# SCH_RiberyController_2024-03-02.net
KiCad netlist of a schematic drawn in EasyEDA
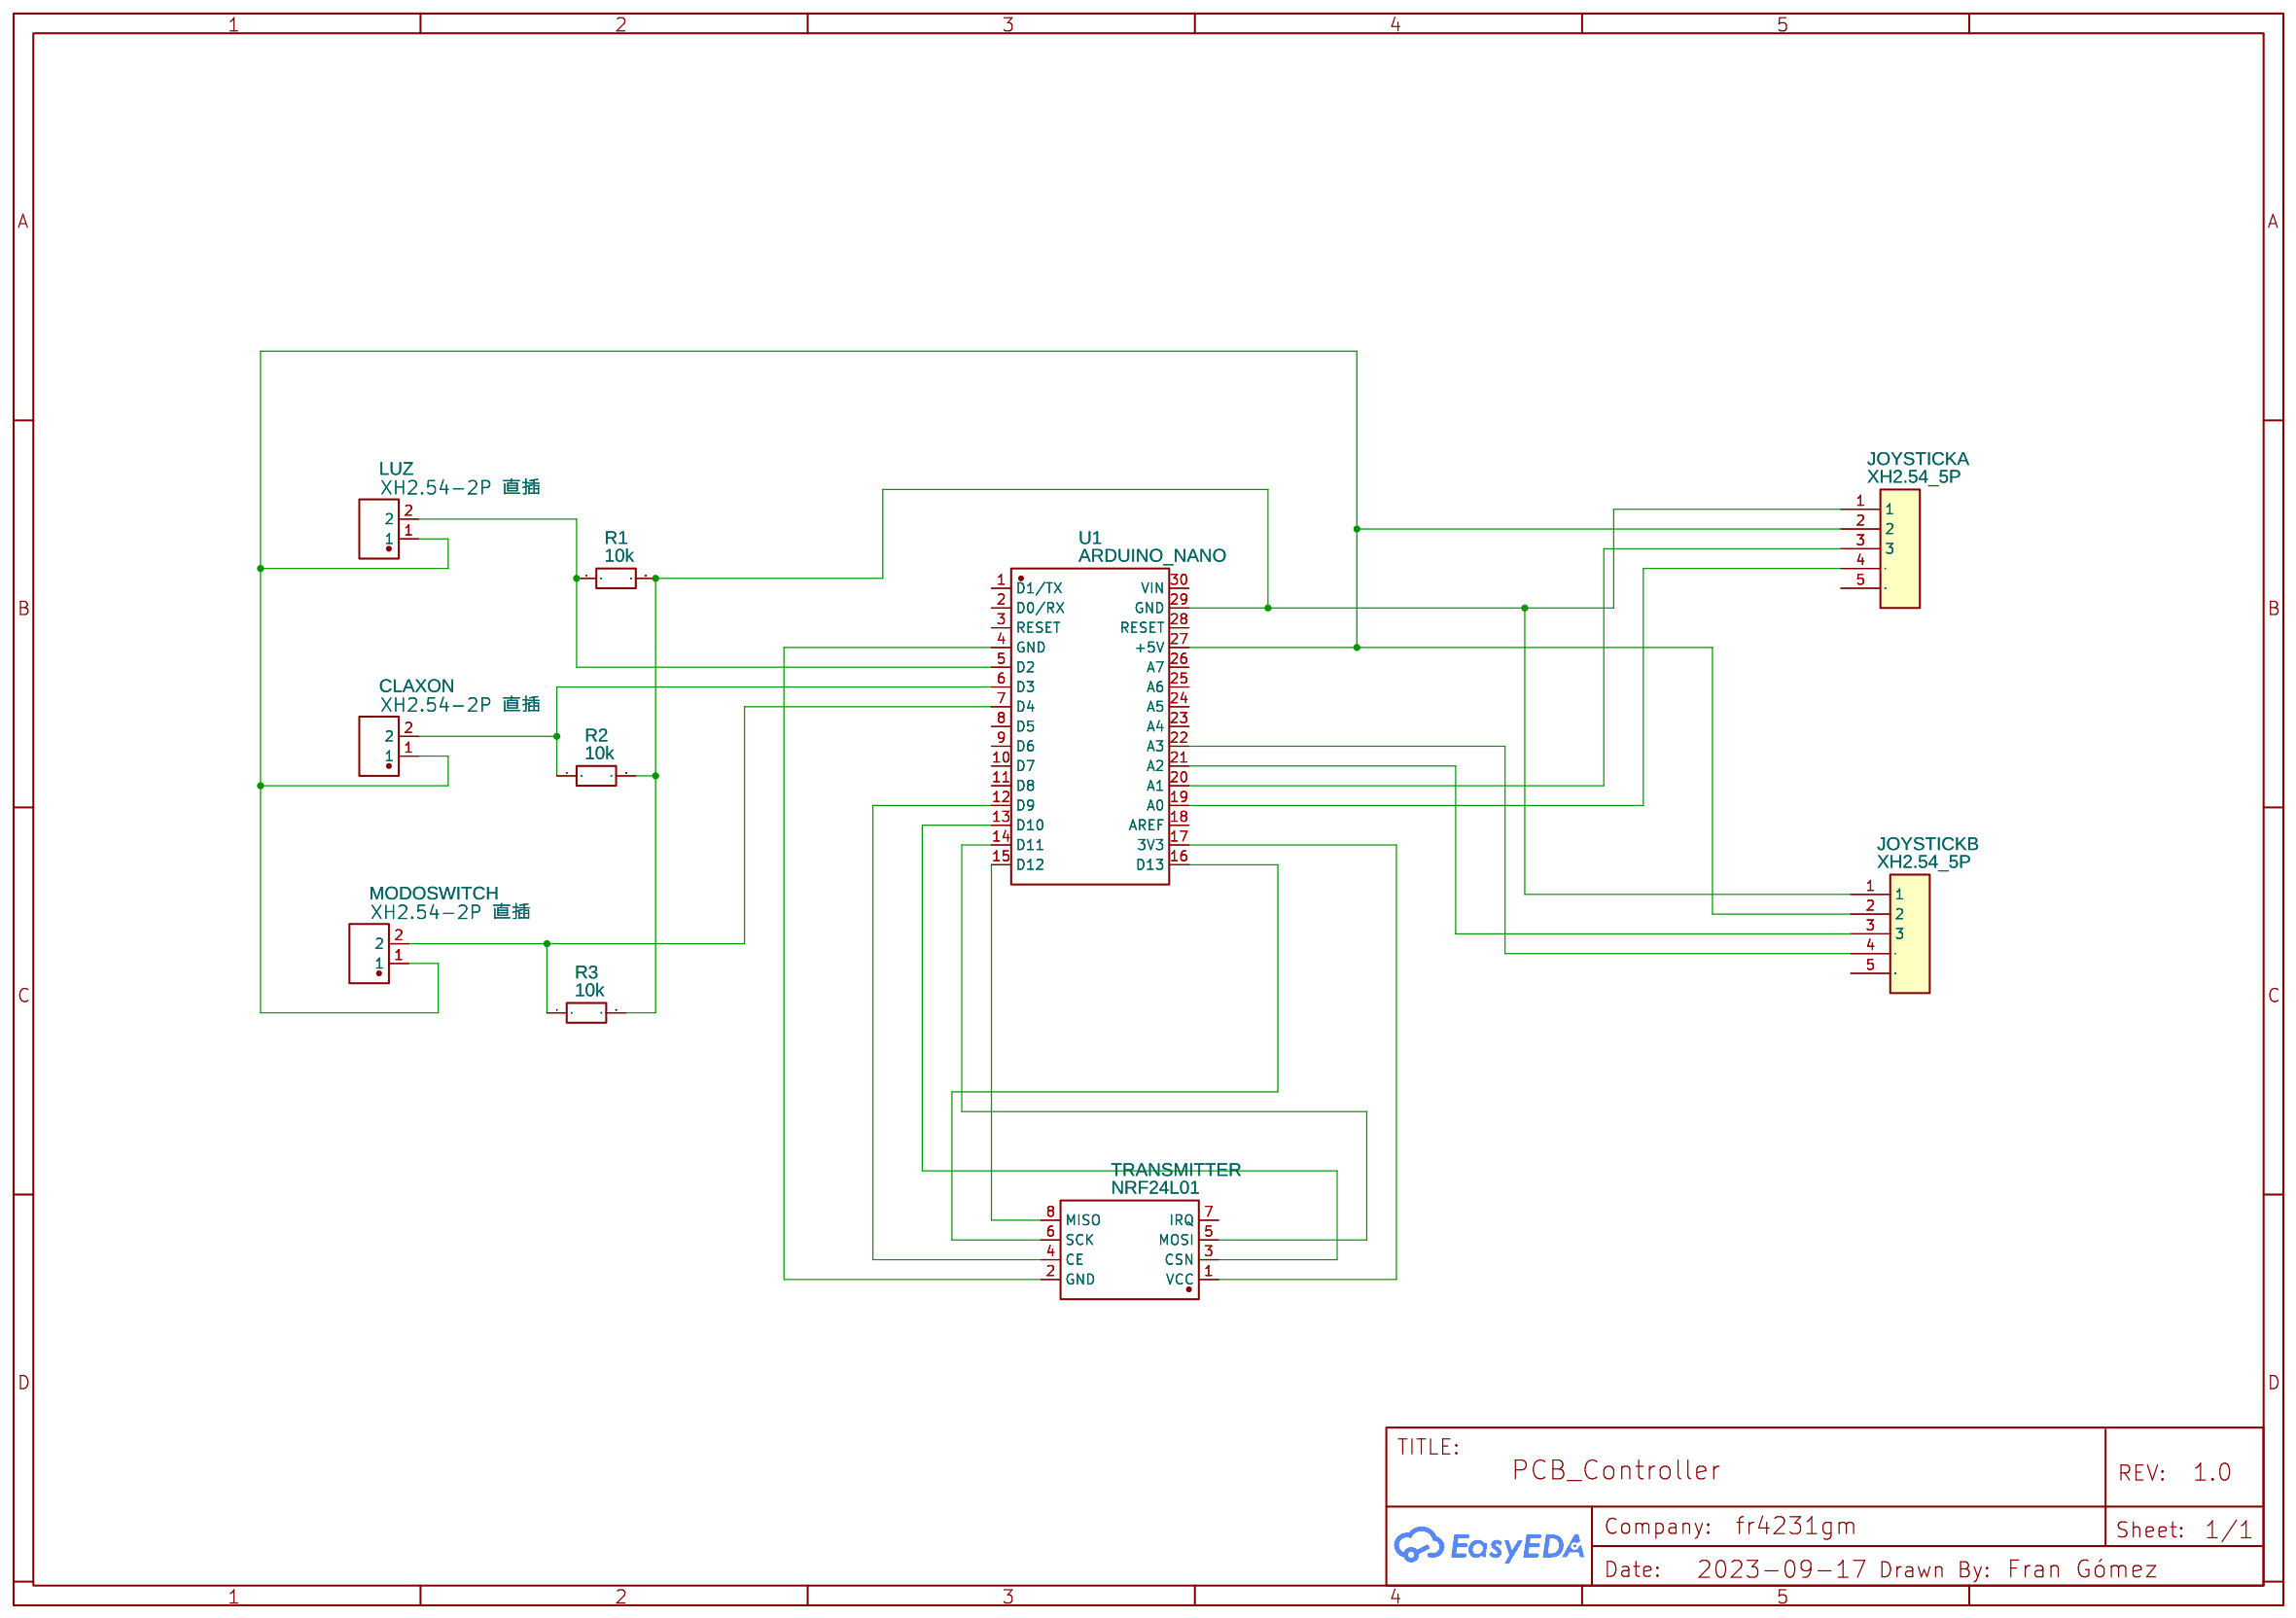
[diagram p0: schematic sheet]

(export (version "E")
  (design (tool "Eeschema 10.0.6"))
  (components
    (comp (ref "CLAXON") (value "XH2.54-2P 直插") (libsource (lib "") (part "XH2.54-2P 直插_2")))
    (comp (ref "JOYSTICKA")
      (value "XH2.54_5P")
      (fields (field (name "Manufacturer Part") "XH2.54_3P"))
      (libsource (lib "") (part "XH2.54_5P_1"))
    )
    (comp (ref "JOYSTICKB")
      (value "XH2.54_5P")
      (fields (field (name "Manufacturer Part") "XH2.54_3P"))
      (libsource (lib "") (part "XH2.54_5P"))
    )
    (comp (ref "LUZ") (value "XH2.54-2P 直插") (libsource (lib "") (part "XH2.54-2P 直插")))
    (comp (ref "MODOSWITCH") (value "XH2.54-2P 直插") (libsource (lib "") (part "XH2.54-2P 直插_1")))
    (comp (ref "R1") (value "10k") (libsource (lib "") (part "R_AXIAL-0.3_EU")))
    (comp (ref "R2") (value "10k") (libsource (lib "") (part "R_AXIAL-0.3_EU")))
    (comp (ref "R3") (value "10k") (libsource (lib "") (part "R_AXIAL-0.3_EU")))
    (comp (ref "TRANSMITTER")
      (value "NRF24L01")
      (fields (field (name "Manufacturer Part") "NF-04") (field (name "Manufacturer") "Ai-Thinker(安信可)"))
      (libsource (lib "") (part "NRF24L01"))
    )
    (comp (ref "U1") (value "ARDUINO_NANO") (libsource (lib "") (part "ARDUINO_NANO")))
  )
  (nets
    (net (code "1") (name "Net-(JOYSTICKA-Pad1)") (class "Default")
      (node (ref "JOYSTICKA") (pin "1") (pinfunction "1_1") (pintype "unspecified"))
      (node (ref "JOYSTICKB") (pin "1") (pinfunction "1_1") (pintype "unspecified"))
      (node (ref "R1") (pin "2") (pinfunction "2_2") (pintype "unspecified"))
      (node (ref "R2") (pin "2") (pinfunction "2_2") (pintype "unspecified"))
      (node (ref "R3") (pin "2") (pinfunction "2_2") (pintype "unspecified"))
      (node (ref "U1") (pin "29") (pinfunction "GND_29") (pintype "unspecified"))
    )
    (net (code "2") (name "Net-(TRANSMITTER-CE)") (class "Default")
      (node (ref "TRANSMITTER") (pin "4") (pinfunction "CE_4") (pintype "unspecified"))
      (node (ref "U1") (pin "12") (pinfunction "D9_12") (pintype "unspecified"))
    )
    (net (code "3") (name "Net-(TRANSMITTER-CSN)") (class "Default")
      (node (ref "TRANSMITTER") (pin "3") (pinfunction "CSN_3") (pintype "unspecified"))
      (node (ref "U1") (pin "13") (pinfunction "D10_13") (pintype "unspecified"))
    )
    (net (code "4") (name "Net-(TRANSMITTER-GND)") (class "Default")
      (node (ref "TRANSMITTER") (pin "2") (pinfunction "GND_2") (pintype "unspecified"))
      (node (ref "U1") (pin "4") (pinfunction "GND_4") (pintype "unspecified"))
    )
    (net (code "5") (name "Net-(TRANSMITTER-MISO)") (class "Default")
      (node (ref "TRANSMITTER") (pin "8") (pinfunction "MISO_8") (pintype "unspecified"))
      (node (ref "U1") (pin "15") (pinfunction "D12_15") (pintype "unspecified"))
    )
    (net (code "6") (name "Net-(TRANSMITTER-MOSI)") (class "Default")
      (node (ref "TRANSMITTER") (pin "5") (pinfunction "MOSI_5") (pintype "unspecified"))
      (node (ref "U1") (pin "14") (pinfunction "D11_14") (pintype "unspecified"))
    )
    (net (code "7") (name "Net-(TRANSMITTER-SCK)") (class "Default")
      (node (ref "TRANSMITTER") (pin "6") (pinfunction "SCK_6") (pintype "unspecified"))
      (node (ref "U1") (pin "16") (pinfunction "D13_16") (pintype "unspecified"))
    )
    (net (code "8") (name "Net-(TRANSMITTER-VCC)") (class "Default")
      (node (ref "TRANSMITTER") (pin "1") (pinfunction "VCC_1") (pintype "unspecified"))
      (node (ref "U1") (pin "17") (pinfunction "3V3_17") (pintype "unspecified"))
    )
    (net (code "9") (name "Net-(U1-+5V)") (class "Default")
      (node (ref "CLAXON") (pin "1") (pinfunction "1_1") (pintype "unspecified"))
      (node (ref "JOYSTICKA") (pin "2") (pinfunction "2_2") (pintype "unspecified"))
      (node (ref "JOYSTICKB") (pin "2") (pinfunction "2_2") (pintype "unspecified"))
      (node (ref "LUZ") (pin "1") (pinfunction "1_1") (pintype "unspecified"))
      (node (ref "MODOSWITCH") (pin "1") (pinfunction "1_1") (pintype "unspecified"))
      (node (ref "U1") (pin "27") (pinfunction "+5V_27") (pintype "unspecified"))
    )
    (net (code "10") (name "Net-(U1-A0)") (class "Default")
      (node (ref "JOYSTICKA") (pin "4") (pinfunction "4_4") (pintype "unspecified"))
      (node (ref "U1") (pin "19") (pinfunction "A0_19") (pintype "unspecified"))
    )
    (net (code "11") (name "Net-(U1-A1)") (class "Default")
      (node (ref "JOYSTICKA") (pin "3") (pinfunction "3_3") (pintype "unspecified"))
      (node (ref "U1") (pin "20") (pinfunction "A1_20") (pintype "unspecified"))
    )
    (net (code "12") (name "Net-(U1-A2)") (class "Default")
      (node (ref "JOYSTICKB") (pin "3") (pinfunction "3_3") (pintype "unspecified"))
      (node (ref "U1") (pin "21") (pinfunction "A2_21") (pintype "unspecified"))
    )
    (net (code "13") (name "Net-(U1-A3)") (class "Default")
      (node (ref "JOYSTICKB") (pin "4") (pinfunction "4_4") (pintype "unspecified"))
      (node (ref "U1") (pin "22") (pinfunction "A3_22") (pintype "unspecified"))
    )
    (net (code "14") (name "Net-(U1-D2)") (class "Default")
      (node (ref "LUZ") (pin "2") (pinfunction "2_2") (pintype "unspecified"))
      (node (ref "R1") (pin "1") (pinfunction "1_1") (pintype "unspecified"))
      (node (ref "U1") (pin "5") (pinfunction "D2_5") (pintype "unspecified"))
    )
    (net (code "15") (name "Net-(U1-D3)") (class "Default")
      (node (ref "CLAXON") (pin "2") (pinfunction "2_2") (pintype "unspecified"))
      (node (ref "R2") (pin "1") (pinfunction "1_1") (pintype "unspecified"))
      (node (ref "U1") (pin "6") (pinfunction "D3_6") (pintype "unspecified"))
    )
    (net (code "16") (name "Net-(U1-D4)") (class "Default")
      (node (ref "MODOSWITCH") (pin "2") (pinfunction "2_2") (pintype "unspecified"))
      (node (ref "R3") (pin "1") (pinfunction "1_1") (pintype "unspecified"))
      (node (ref "U1") (pin "7") (pinfunction "D4_7") (pintype "unspecified"))
    )
    (net (code "17") (name "unconnected-(JOYSTICKA-Pad5)") (class "Default")
      (node (ref "JOYSTICKA") (pin "5") (pinfunction "5_5") (pintype "unspecified"))
    )
    (net (code "18") (name "unconnected-(JOYSTICKB-Pad5)") (class "Default")
      (node (ref "JOYSTICKB") (pin "5") (pinfunction "5_5") (pintype "unspecified"))
    )
    (net (code "19") (name "unconnected-(TRANSMITTER-IRQ-Pad7)") (class "Default")
      (node (ref "TRANSMITTER") (pin "7") (pinfunction "IRQ_7") (pintype "unspecified"))
    )
    (net (code "20") (name "unconnected-(U1-A4-Pad23)") (class "Default")
      (node (ref "U1") (pin "23") (pinfunction "A4_23") (pintype "unspecified"))
    )
    (net (code "21") (name "unconnected-(U1-A5-Pad24)") (class "Default")
      (node (ref "U1") (pin "24") (pinfunction "A5_24") (pintype "unspecified"))
    )
    (net (code "22") (name "unconnected-(U1-A6-Pad25)") (class "Default")
      (node (ref "U1") (pin "25") (pinfunction "A6_25") (pintype "unspecified"))
    )
    (net (code "23") (name "unconnected-(U1-A7-Pad26)") (class "Default")
      (node (ref "U1") (pin "26") (pinfunction "A7_26") (pintype "unspecified"))
    )
    (net (code "24") (name "unconnected-(U1-AREF-Pad18)") (class "Default")
      (node (ref "U1") (pin "18") (pinfunction "AREF_18") (pintype "unspecified"))
    )
    (net (code "25") (name "unconnected-(U1-D0{slash}RX-Pad2)") (class "Default")
      (node (ref "U1") (pin "2") (pinfunction "D0/RX_2") (pintype "unspecified"))
    )
    (net (code "26") (name "unconnected-(U1-D1{slash}TX-Pad1)") (class "Default")
      (node (ref "U1") (pin "1") (pinfunction "D1/TX_1") (pintype "unspecified"))
    )
    (net (code "27") (name "unconnected-(U1-D5-Pad8)") (class "Default")
      (node (ref "U1") (pin "8") (pinfunction "D5_8") (pintype "unspecified"))
    )
    (net (code "28") (name "unconnected-(U1-D6-Pad9)") (class "Default")
      (node (ref "U1") (pin "9") (pinfunction "D6_9") (pintype "unspecified"))
    )
    (net (code "29") (name "unconnected-(U1-D7-Pad10)") (class "Default")
      (node (ref "U1") (pin "10") (pinfunction "D7_10") (pintype "unspecified"))
    )
    (net (code "30") (name "unconnected-(U1-D8-Pad11)") (class "Default")
      (node (ref "U1") (pin "11") (pinfunction "D8_11") (pintype "unspecified"))
    )
    (net (code "31") (name "unconnected-(U1-RESET-Pad3)") (class "Default")
      (node (ref "U1") (pin "3") (pinfunction "RESET_3") (pintype "unspecified"))
    )
    (net (code "32") (name "unconnected-(U1-RESET-Pad28)") (class "Default")
      (node (ref "U1") (pin "28") (pinfunction "RESET_28") (pintype "unspecified"))
    )
    (net (code "33") (name "unconnected-(U1-VIN-Pad30)") (class "Default")
      (node (ref "U1") (pin "30") (pinfunction "VIN_30") (pintype "unspecified"))
    )
  )
)
